# Sheet1.net
KiCad netlist of a schematic drawn in Altium Designer
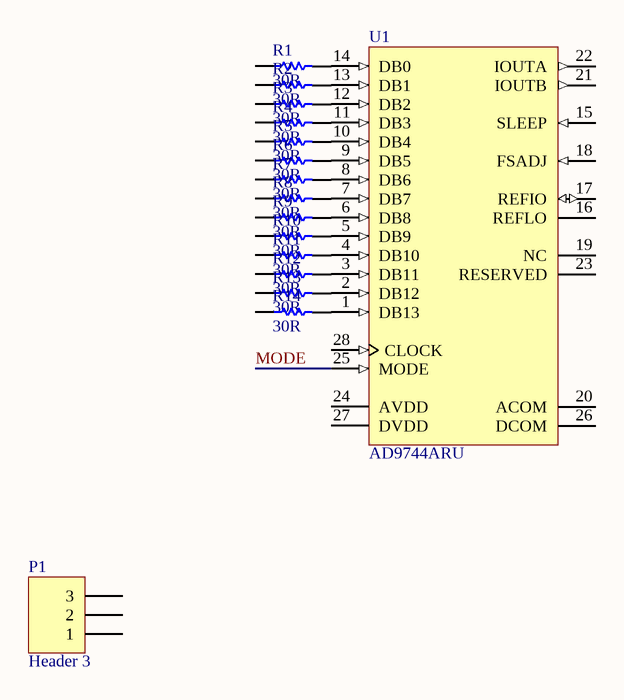
[diagram p0: Sheet1.SchDoc]

(export (version "E")
  (design (tool "Eeschema 10.0.6"))
  (components
    (comp (ref "P1")
      (value "Header 3")
      (footprint "HDR1X3")
      (description "Header, 3-Pin")
      (fields (field (name "PUBLISHER") "Altium Limited"))
      (libsource (lib "Miscellaneous Connectors") (part "Header 3"))
    )
    (comp (ref "R1") (value "30R") (footprint "0805") (libsource (lib "Schlib1") (part "Res")))
    (comp (ref "R2") (value "30R") (footprint "0805") (libsource (lib "Schlib1") (part "Res")))
    (comp (ref "R3") (value "30R") (footprint "0805") (libsource (lib "Schlib1") (part "Res")))
    (comp (ref "R4") (value "30R") (footprint "0805") (libsource (lib "Schlib1") (part "Res")))
    (comp (ref "R5") (value "30R") (footprint "0805") (libsource (lib "Schlib1") (part "Res")))
    (comp (ref "R6") (value "30R") (footprint "0805") (libsource (lib "Schlib1") (part "Res")))
    (comp (ref "R7") (value "30R") (footprint "0805") (libsource (lib "Schlib1") (part "Res")))
    (comp (ref "R8") (value "30R") (footprint "0805") (libsource (lib "Schlib1") (part "Res")))
    (comp (ref "R9") (value "30R") (footprint "0805") (libsource (lib "Schlib1") (part "Res")))
    (comp (ref "R10") (value "30R") (footprint "0805") (libsource (lib "Schlib1") (part "Res")))
    (comp (ref "R11") (value "30R") (footprint "0805") (libsource (lib "Schlib1") (part "Res")))
    (comp (ref "R12") (value "30R") (footprint "0805") (libsource (lib "Schlib1") (part "Res")))
    (comp (ref "R13") (value "30R") (footprint "0805") (libsource (lib "Schlib1") (part "Res")))
    (comp (ref "R14") (value "30R") (footprint "0805") (libsource (lib "Schlib1") (part "Res")))
    (comp (ref "U1")
      (value "AD9744ARU")
      (footprint "RU-28_N")
      (description "Single 14-Bit TxDAC, 210 Msps, -40 to +85 degC, RU-28, Tube")
      (fields (field (name "GENERIC PART NUMBER") "AD9744") (field (name "MANUFACTURER") "Analog Devices"))
      (libsource (lib "Schlib1") (part "AD9744ARU"))
    )
  )
  (nets
    (net (code "1") (name "/MODE") (class "Default")
      (node (ref "U1") (pin "25") (pinfunction "MODE_25") (pintype "input"))
    )
    (net (code "2") (name "Net-(U1-DB0)") (class "Default")
      (node (ref "R1") (pin "2") (pinfunction "2_2") (pintype "passive"))
      (node (ref "U1") (pin "14") (pinfunction "DB0_14") (pintype "input"))
    )
    (net (code "3") (name "Net-(U1-DB1)") (class "Default")
      (node (ref "R2") (pin "2") (pinfunction "2_2") (pintype "passive"))
      (node (ref "U1") (pin "13") (pinfunction "DB1_13") (pintype "input"))
    )
    (net (code "4") (name "Net-(U1-DB2)") (class "Default")
      (node (ref "R3") (pin "2") (pinfunction "2_2") (pintype "passive"))
      (node (ref "U1") (pin "12") (pinfunction "DB2_12") (pintype "input"))
    )
    (net (code "5") (name "Net-(U1-DB3)") (class "Default")
      (node (ref "R4") (pin "2") (pinfunction "2_2") (pintype "passive"))
      (node (ref "U1") (pin "11") (pinfunction "DB3_11") (pintype "input"))
    )
    (net (code "6") (name "Net-(U1-DB4)") (class "Default")
      (node (ref "R5") (pin "2") (pinfunction "2_2") (pintype "passive"))
      (node (ref "U1") (pin "10") (pinfunction "DB4_10") (pintype "input"))
    )
    (net (code "7") (name "Net-(U1-DB5)") (class "Default")
      (node (ref "R6") (pin "2") (pinfunction "2_2") (pintype "passive"))
      (node (ref "U1") (pin "9") (pinfunction "DB5_9") (pintype "input"))
    )
    (net (code "8") (name "Net-(U1-DB6)") (class "Default")
      (node (ref "R7") (pin "2") (pinfunction "2_2") (pintype "passive"))
      (node (ref "U1") (pin "8") (pinfunction "DB6_8") (pintype "input"))
    )
    (net (code "9") (name "Net-(U1-DB7)") (class "Default")
      (node (ref "R8") (pin "2") (pinfunction "2_2") (pintype "passive"))
      (node (ref "U1") (pin "7") (pinfunction "DB7_7") (pintype "input"))
    )
    (net (code "10") (name "Net-(U1-DB8)") (class "Default")
      (node (ref "R9") (pin "2") (pinfunction "2_2") (pintype "passive"))
      (node (ref "U1") (pin "6") (pinfunction "DB8_6") (pintype "input"))
    )
    (net (code "11") (name "Net-(U1-DB9)") (class "Default")
      (node (ref "R10") (pin "2") (pinfunction "2_2") (pintype "passive"))
      (node (ref "U1") (pin "5") (pinfunction "DB9_5") (pintype "input"))
    )
    (net (code "12") (name "Net-(U1-DB10)") (class "Default")
      (node (ref "R11") (pin "2") (pinfunction "2_2") (pintype "passive"))
      (node (ref "U1") (pin "4") (pinfunction "DB10_4") (pintype "input"))
    )
    (net (code "13") (name "Net-(U1-DB11)") (class "Default")
      (node (ref "R12") (pin "2") (pinfunction "2_2") (pintype "passive"))
      (node (ref "U1") (pin "3") (pinfunction "DB11_3") (pintype "input"))
    )
    (net (code "14") (name "Net-(U1-DB12)") (class "Default")
      (node (ref "R13") (pin "2") (pinfunction "2_2") (pintype "passive"))
      (node (ref "U1") (pin "2") (pinfunction "DB12_2") (pintype "input"))
    )
    (net (code "15") (name "Net-(U1-DB13)") (class "Default")
      (node (ref "R14") (pin "2") (pinfunction "2_2") (pintype "passive"))
      (node (ref "U1") (pin "1") (pinfunction "DB13_1") (pintype "input"))
    )
    (net (code "16") (name "unconnected-(P1-Pad1)") (class "Default")
      (node (ref "P1") (pin "1") (pinfunction "1_1") (pintype "passive"))
    )
    (net (code "17") (name "unconnected-(P1-Pad2)") (class "Default")
      (node (ref "P1") (pin "2") (pinfunction "2_2") (pintype "passive"))
    )
    (net (code "18") (name "unconnected-(P1-Pad3)") (class "Default")
      (node (ref "P1") (pin "3") (pinfunction "3_3") (pintype "passive"))
    )
    (net (code "19") (name "unconnected-(R1-Pad1)") (class "Default")
      (node (ref "R1") (pin "1") (pinfunction "1_1") (pintype "passive"))
    )
    (net (code "20") (name "unconnected-(R2-Pad1)") (class "Default")
      (node (ref "R2") (pin "1") (pinfunction "1_1") (pintype "passive"))
    )
    (net (code "21") (name "unconnected-(R3-Pad1)") (class "Default")
      (node (ref "R3") (pin "1") (pinfunction "1_1") (pintype "passive"))
    )
    (net (code "22") (name "unconnected-(R4-Pad1)") (class "Default")
      (node (ref "R4") (pin "1") (pinfunction "1_1") (pintype "passive"))
    )
    (net (code "23") (name "unconnected-(R5-Pad1)") (class "Default")
      (node (ref "R5") (pin "1") (pinfunction "1_1") (pintype "passive"))
    )
    (net (code "24") (name "unconnected-(R6-Pad1)") (class "Default")
      (node (ref "R6") (pin "1") (pinfunction "1_1") (pintype "passive"))
    )
    (net (code "25") (name "unconnected-(R7-Pad1)") (class "Default")
      (node (ref "R7") (pin "1") (pinfunction "1_1") (pintype "passive"))
    )
    (net (code "26") (name "unconnected-(R8-Pad1)") (class "Default")
      (node (ref "R8") (pin "1") (pinfunction "1_1") (pintype "passive"))
    )
    (net (code "27") (name "unconnected-(R9-Pad1)") (class "Default")
      (node (ref "R9") (pin "1") (pinfunction "1_1") (pintype "passive"))
    )
    (net (code "28") (name "unconnected-(R10-Pad1)") (class "Default")
      (node (ref "R10") (pin "1") (pinfunction "1_1") (pintype "passive"))
    )
    (net (code "29") (name "unconnected-(R11-Pad1)") (class "Default")
      (node (ref "R11") (pin "1") (pinfunction "1_1") (pintype "passive"))
    )
    (net (code "30") (name "unconnected-(R12-Pad1)") (class "Default")
      (node (ref "R12") (pin "1") (pinfunction "1_1") (pintype "passive"))
    )
    (net (code "31") (name "unconnected-(R13-Pad1)") (class "Default")
      (node (ref "R13") (pin "1") (pinfunction "1_1") (pintype "passive"))
    )
    (net (code "32") (name "unconnected-(R14-Pad1)") (class "Default")
      (node (ref "R14") (pin "1") (pinfunction "1_1") (pintype "passive"))
    )
    (net (code "33") (name "unconnected-(U1-ACOM-Pad20)") (class "Default")
      (node (ref "U1") (pin "20") (pinfunction "ACOM_20") (pintype "power_in"))
    )
    (net (code "34") (name "unconnected-(U1-AVDD-Pad24)") (class "Default")
      (node (ref "U1") (pin "24") (pinfunction "AVDD_24") (pintype "power_in"))
    )
    (net (code "35") (name "unconnected-(U1-CLOCK-Pad28)") (class "Default")
      (node (ref "U1") (pin "28") (pinfunction "CLOCK_28") (pintype "input"))
    )
    (net (code "36") (name "unconnected-(U1-DCOM-Pad26)") (class "Default")
      (node (ref "U1") (pin "26") (pinfunction "DCOM_26") (pintype "power_in"))
    )
    (net (code "37") (name "unconnected-(U1-DVDD-Pad27)") (class "Default")
      (node (ref "U1") (pin "27") (pinfunction "DVDD_27") (pintype "power_in"))
    )
    (net (code "38") (name "unconnected-(U1-FSADJ-Pad18)") (class "Default")
      (node (ref "U1") (pin "18") (pinfunction "FSADJ_18") (pintype "input"))
    )
    (net (code "39") (name "unconnected-(U1-IOUTA-Pad22)") (class "Default")
      (node (ref "U1") (pin "22") (pinfunction "IOUTA_22") (pintype "output"))
    )
    (net (code "40") (name "unconnected-(U1-IOUTB-Pad21)") (class "Default")
      (node (ref "U1") (pin "21") (pinfunction "IOUTB_21") (pintype "output"))
    )
    (net (code "41") (name "unconnected-(U1-NC-Pad19)") (class "Default")
      (node (ref "U1") (pin "19") (pinfunction "NC_19") (pintype "passive"))
    )
    (net (code "42") (name "unconnected-(U1-REFIO-Pad17)") (class "Default")
      (node (ref "U1") (pin "17") (pinfunction "REFIO_17") (pintype "bidirectional"))
    )
    (net (code "43") (name "unconnected-(U1-REFLO-Pad16)") (class "Default")
      (node (ref "U1") (pin "16") (pinfunction "REFLO_16") (pintype "passive"))
    )
    (net (code "44") (name "unconnected-(U1-RESERVED-Pad23)") (class "Default")
      (node (ref "U1") (pin "23") (pinfunction "RESERVED_23") (pintype "passive"))
    )
    (net (code "45") (name "unconnected-(U1-SLEEP-Pad15)") (class "Default")
      (node (ref "U1") (pin "15") (pinfunction "SLEEP_15") (pintype "input"))
    )
  )
)
